# shield-rs422.net
KiCad netlist of a schematic drawn in EAGLE
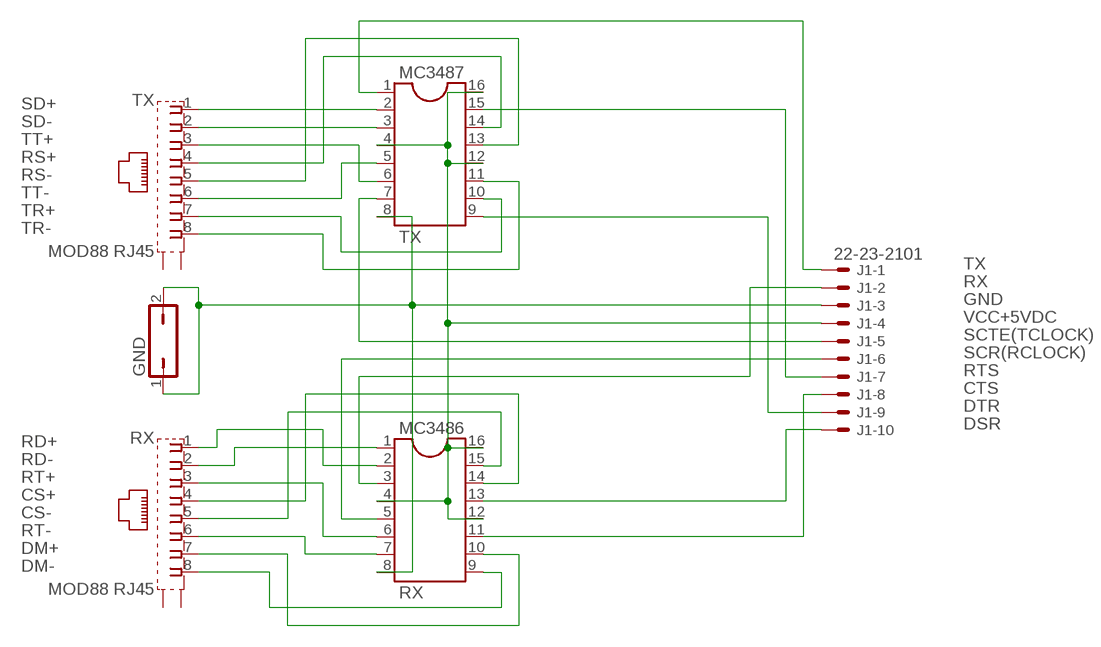
[diagram p0: schematic, sheet 1]

(export (version "E")
  (design (tool "Eeschema 10.0.6"))
  (components
    (comp (ref "GND")
      (value "JP1Q")
      (footprint "eagle-import:JP1")
      (libsource (lib "eagle-import") (part "JP1Q"))
    )
    (comp (ref "J1")
      (value "22-23-2101")
      (footprint "eagle-import:22-23-2101")
      (fields (field (name "MF") "MOLEX"))
      (libsource (lib "eagle-import") (part "22-23-2101"))
    )
    (comp (ref "MC3486")
      (value "RX")
      (footprint "eagle-import:DIL16")
      (libsource (lib "eagle-import") (part "DIL16"))
    )
    (comp (ref "MC3487")
      (value "TX")
      (footprint "eagle-import:DIL16")
      (libsource (lib "eagle-import") (part "DIL16"))
    )
    (comp (ref "RX")
      (value "MOD88 RJ45")
      (footprint "eagle-import:GLX-S-88M")
      (libsource (lib "eagle-import") (part "GLX-S-88M"))
    )
    (comp (ref "TX")
      (value "MOD88 RJ45")
      (footprint "eagle-import:GLX-S-88M")
      (libsource (lib "eagle-import") (part "GLX-S-88M"))
    )
  )
  (nets
    (net (code "1") (name "/CS+") (class "Default")
      (node (ref "MC3486") (pin "14") (pinfunction "14_14") (pintype "passive"))
      (node (ref "RX") (pin "4") (pinfunction "4_4") (pintype "passive"))
    )
    (net (code "2") (name "/CS-") (class "Default")
      (node (ref "MC3486") (pin "15") (pinfunction "15_15") (pintype "passive"))
      (node (ref "RX") (pin "5") (pinfunction "5_5") (pintype "passive"))
    )
    (net (code "3") (name "/CTS") (class "Default")
      (node (ref "J1") (pin "8") (pinfunction "S_8") (pintype "passive"))
      (node (ref "MC3486") (pin "11") (pinfunction "11_11") (pintype "passive"))
    )
    (net (code "4") (name "/DM+") (class "Default")
      (node (ref "MC3486") (pin "10") (pinfunction "10_10") (pintype "passive"))
      (node (ref "RX") (pin "7") (pinfunction "7_7") (pintype "passive"))
    )
    (net (code "5") (name "/DM-") (class "Default")
      (node (ref "MC3486") (pin "9") (pinfunction "9_9") (pintype "passive"))
      (node (ref "RX") (pin "8") (pinfunction "8_8") (pintype "passive"))
    )
    (net (code "6") (name "/DSR") (class "Default")
      (node (ref "J1") (pin "10") (pinfunction "S_10") (pintype "passive"))
      (node (ref "MC3486") (pin "13") (pinfunction "13_13") (pintype "passive"))
    )
    (net (code "7") (name "/DTR") (class "Default")
      (node (ref "J1") (pin "9") (pinfunction "S_9") (pintype "passive"))
      (node (ref "MC3487") (pin "9") (pinfunction "9_9") (pintype "passive"))
    )
    (net (code "8") (name "/GND") (class "Default")
      (node (ref "GND") (pin "1") (pinfunction "1_1") (pintype "passive"))
      (node (ref "GND") (pin "2") (pinfunction "2_2") (pintype "passive"))
      (node (ref "J1") (pin "3") (pinfunction "S_3") (pintype "passive"))
      (node (ref "MC3486") (pin "8") (pinfunction "8_8") (pintype "passive"))
      (node (ref "MC3487") (pin "8") (pinfunction "8_8") (pintype "passive"))
    )
    (net (code "9") (name "/RD+") (class "Default")
      (node (ref "MC3486") (pin "2") (pinfunction "2_2") (pintype "passive"))
      (node (ref "RX") (pin "1") (pinfunction "1_1") (pintype "passive"))
    )
    (net (code "10") (name "/RD-") (class "Default")
      (node (ref "MC3486") (pin "1") (pinfunction "1_1") (pintype "passive"))
      (node (ref "RX") (pin "2") (pinfunction "2_2") (pintype "passive"))
    )
    (net (code "11") (name "/RS+") (class "Default")
      (node (ref "MC3487") (pin "14") (pinfunction "14_14") (pintype "passive"))
      (node (ref "TX") (pin "4") (pinfunction "4_4") (pintype "passive"))
    )
    (net (code "12") (name "/RS-") (class "Default")
      (node (ref "MC3487") (pin "13") (pinfunction "13_13") (pintype "passive"))
      (node (ref "TX") (pin "5") (pinfunction "5_5") (pintype "passive"))
    )
    (net (code "13") (name "/RT+") (class "Default")
      (node (ref "MC3486") (pin "6") (pinfunction "6_6") (pintype "passive"))
      (node (ref "RX") (pin "3") (pinfunction "3_3") (pintype "passive"))
    )
    (net (code "14") (name "/RT-") (class "Default")
      (node (ref "MC3486") (pin "7") (pinfunction "7_7") (pintype "passive"))
      (node (ref "RX") (pin "6") (pinfunction "6_6") (pintype "passive"))
    )
    (net (code "15") (name "/RTS") (class "Default")
      (node (ref "J1") (pin "7") (pinfunction "S_7") (pintype "passive"))
      (node (ref "MC3487") (pin "15") (pinfunction "15_15") (pintype "passive"))
    )
    (net (code "16") (name "/RX") (class "Default")
      (node (ref "J1") (pin "2") (pinfunction "S_2") (pintype "passive"))
      (node (ref "MC3486") (pin "3") (pinfunction "3_3") (pintype "passive"))
    )
    (net (code "17") (name "/SCR(RCLOCK)") (class "Default")
      (node (ref "J1") (pin "6") (pinfunction "S_6") (pintype "passive"))
      (node (ref "MC3486") (pin "5") (pinfunction "5_5") (pintype "passive"))
    )
    (net (code "18") (name "/SCTE(TCLOCK)") (class "Default")
      (node (ref "J1") (pin "5") (pinfunction "S_5") (pintype "passive"))
      (node (ref "MC3487") (pin "7") (pinfunction "7_7") (pintype "passive"))
    )
    (net (code "19") (name "/SD+") (class "Default")
      (node (ref "MC3487") (pin "2") (pinfunction "2_2") (pintype "passive"))
      (node (ref "TX") (pin "1") (pinfunction "1_1") (pintype "passive"))
    )
    (net (code "20") (name "/SD-") (class "Default")
      (node (ref "MC3487") (pin "3") (pinfunction "3_3") (pintype "passive"))
      (node (ref "TX") (pin "2") (pinfunction "2_2") (pintype "passive"))
    )
    (net (code "21") (name "/TR+") (class "Default")
      (node (ref "MC3487") (pin "10") (pinfunction "10_10") (pintype "passive"))
      (node (ref "TX") (pin "7") (pinfunction "7_7") (pintype "passive"))
    )
    (net (code "22") (name "/TR-") (class "Default")
      (node (ref "MC3487") (pin "11") (pinfunction "11_11") (pintype "passive"))
      (node (ref "TX") (pin "8") (pinfunction "8_8") (pintype "passive"))
    )
    (net (code "23") (name "/TT+") (class "Default")
      (node (ref "MC3487") (pin "6") (pinfunction "6_6") (pintype "passive"))
      (node (ref "TX") (pin "3") (pinfunction "3_3") (pintype "passive"))
    )
    (net (code "24") (name "/TT-") (class "Default")
      (node (ref "MC3487") (pin "5") (pinfunction "5_5") (pintype "passive"))
      (node (ref "TX") (pin "6") (pinfunction "6_6") (pintype "passive"))
    )
    (net (code "25") (name "/TX") (class "Default")
      (node (ref "J1") (pin "1") (pinfunction "S_1") (pintype "passive"))
      (node (ref "MC3487") (pin "1") (pinfunction "1_1") (pintype "passive"))
    )
    (net (code "26") (name "/VCC+5VDC") (class "Default")
      (node (ref "J1") (pin "4") (pinfunction "S_4") (pintype "passive"))
      (node (ref "MC3486") (pin "12") (pinfunction "12_12") (pintype "passive"))
      (node (ref "MC3486") (pin "16") (pinfunction "16_16") (pintype "passive"))
      (node (ref "MC3486") (pin "4") (pinfunction "4_4") (pintype "passive"))
      (node (ref "MC3487") (pin "12") (pinfunction "12_12") (pintype "passive"))
      (node (ref "MC3487") (pin "16") (pinfunction "16_16") (pintype "passive"))
      (node (ref "MC3487") (pin "4") (pinfunction "4_4") (pintype "passive"))
    )
    (net (code "27") (name "unconnected-(RX-PadS1)") (class "Default")
      (node (ref "RX") (pin "S1") (pinfunction "S1_S1") (pintype "passive"))
    )
    (net (code "28") (name "unconnected-(RX-PadS2)") (class "Default")
      (node (ref "RX") (pin "S2") (pinfunction "S2_S2") (pintype "passive"))
    )
    (net (code "29") (name "unconnected-(TX-PadS1)") (class "Default")
      (node (ref "TX") (pin "S1") (pinfunction "S1_S1") (pintype "passive"))
    )
    (net (code "30") (name "unconnected-(TX-PadS2)") (class "Default")
      (node (ref "TX") (pin "S2") (pinfunction "S2_S2") (pintype "passive"))
    )
  )
)
